# Analog_Input.net
KiCad netlist of a schematic drawn in Altium Designer
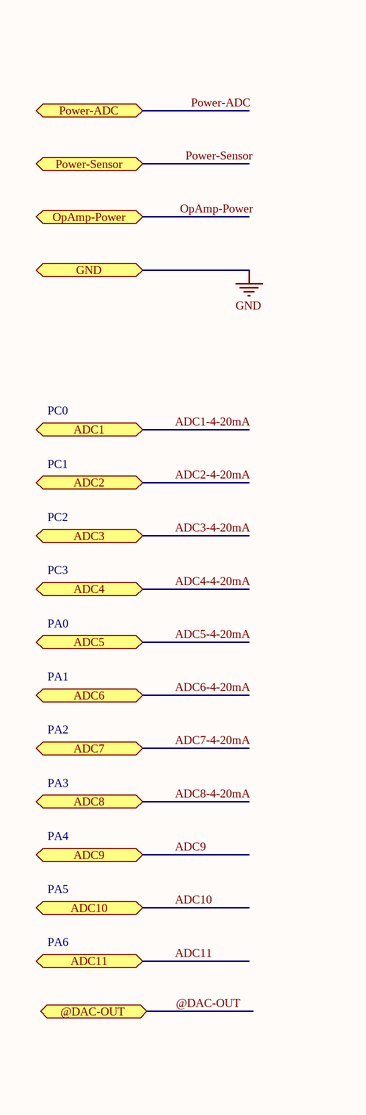
[diagram p0: Analog_Input.SchDoc, top left]
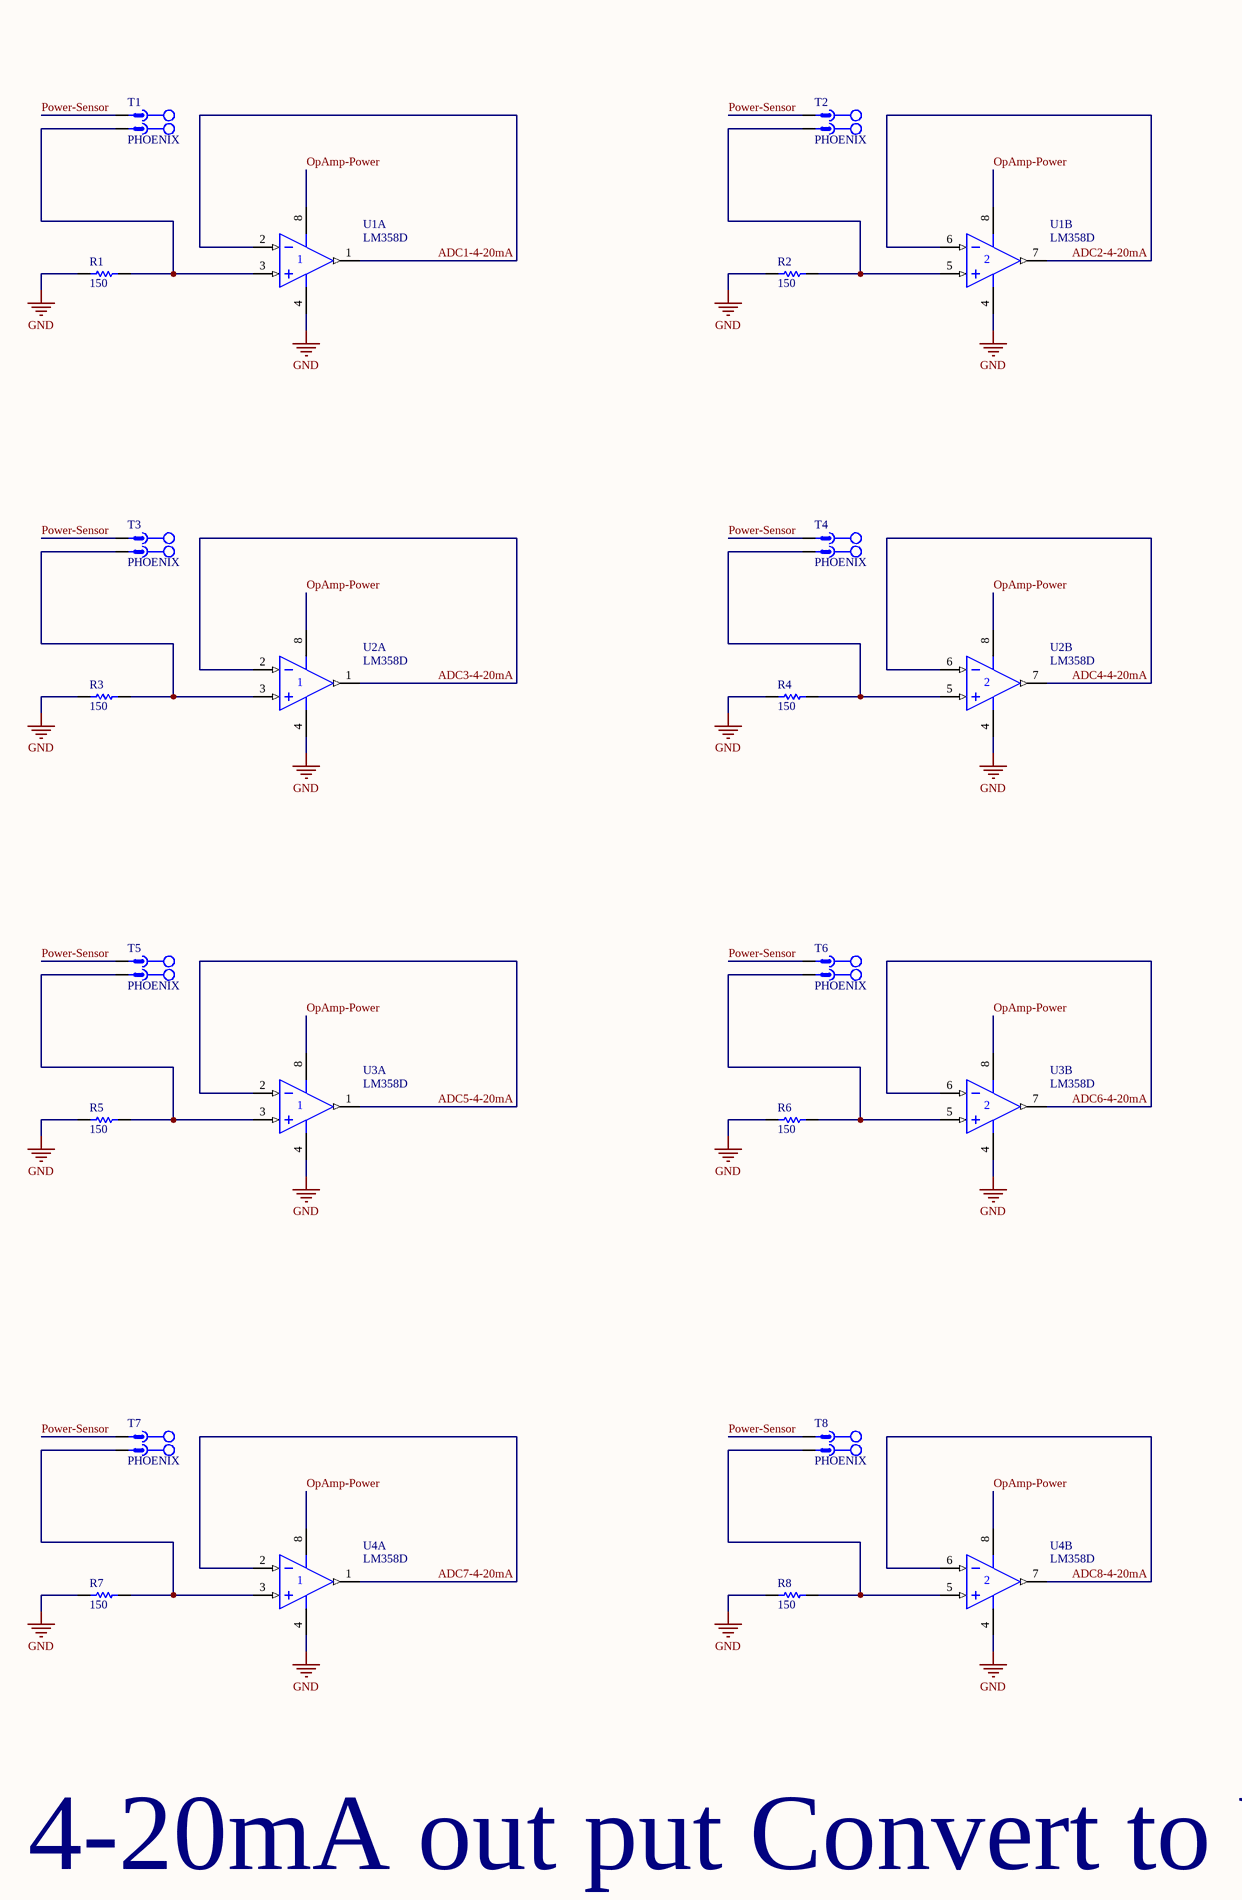
[diagram p1: Analog_Input.SchDoc, top right]
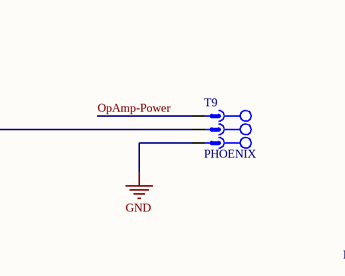
[diagram p2: Analog_Input.SchDoc, bottom left]
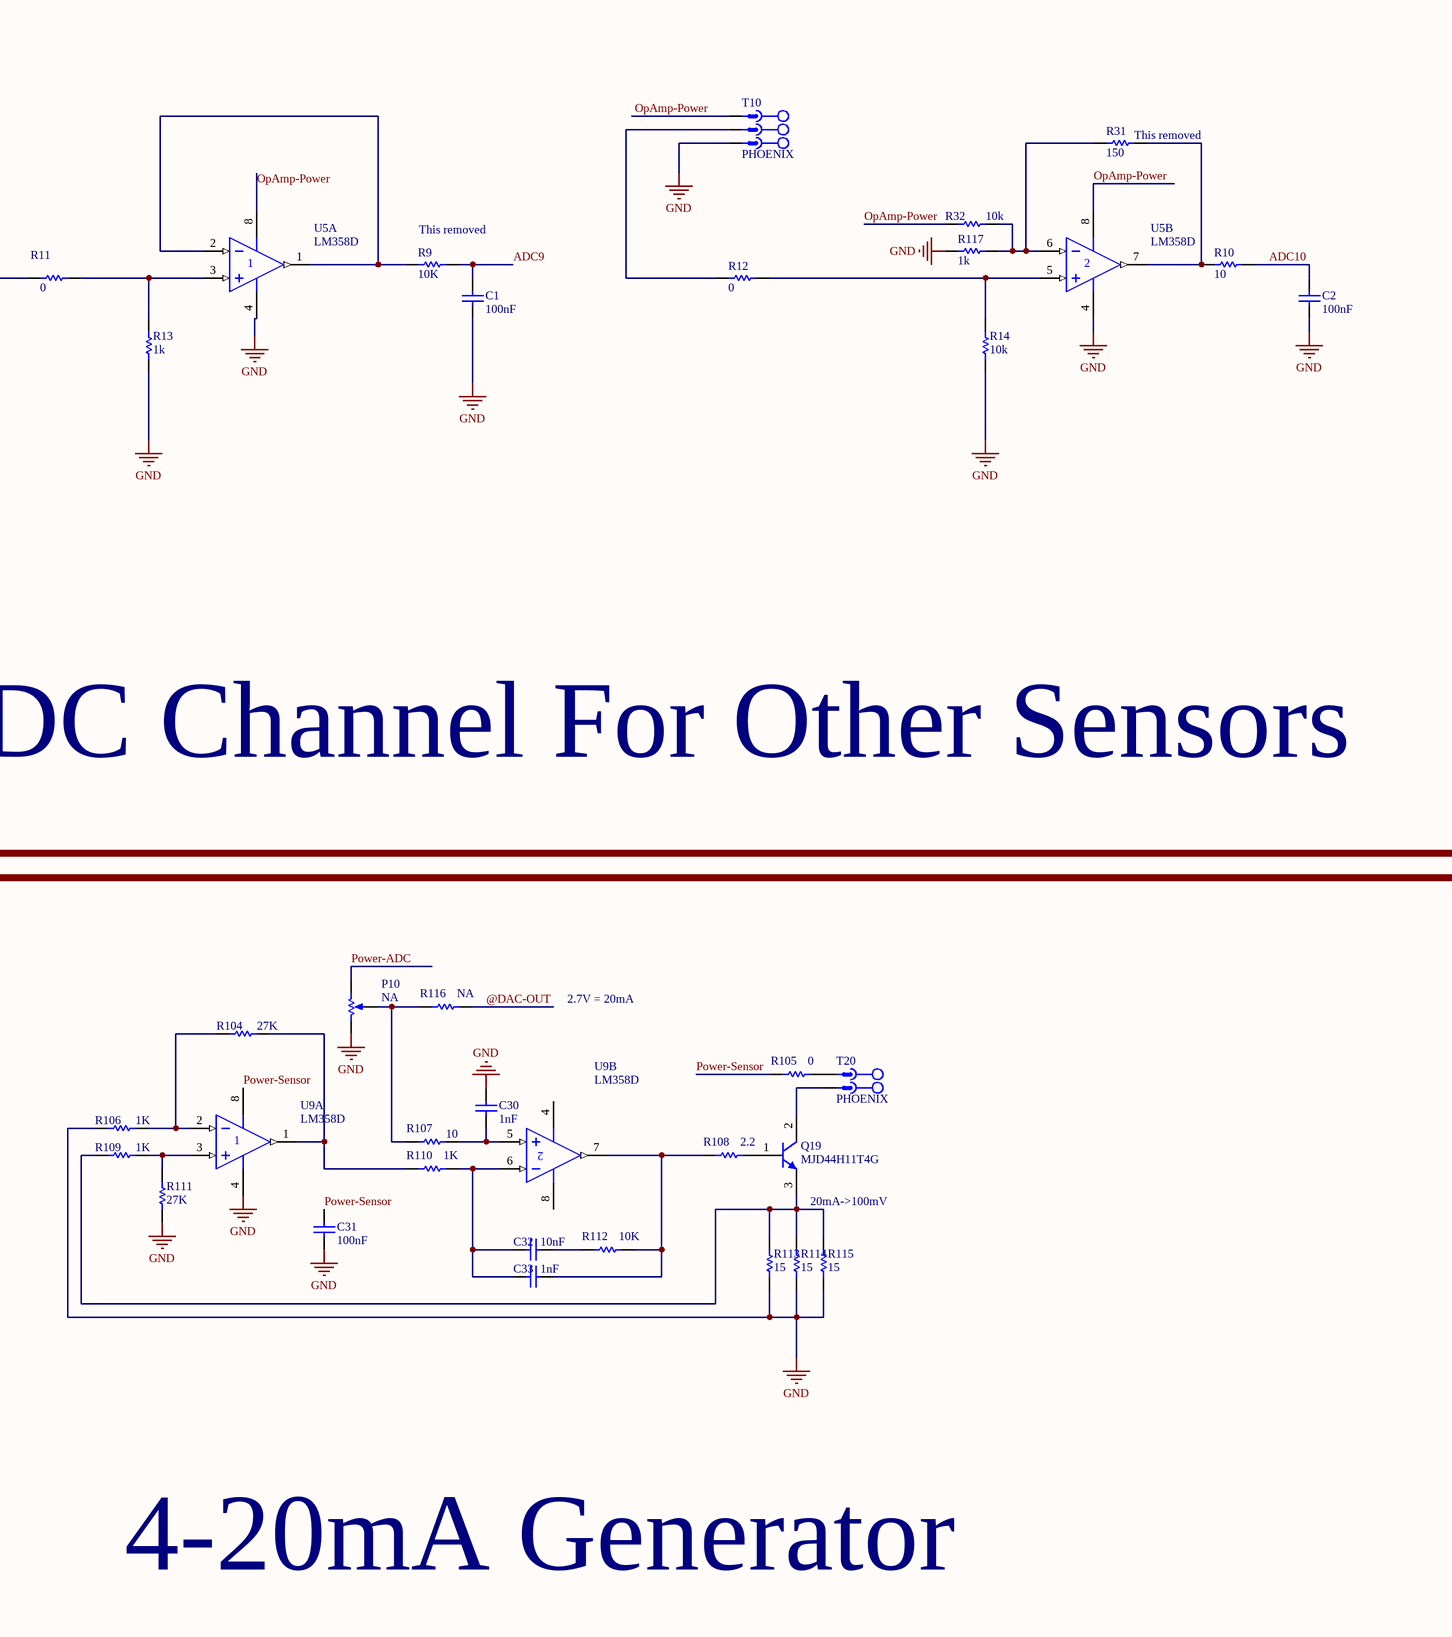
[diagram p3: Analog_Input.SchDoc, bottom right]

(export (version "E")
  (design (tool "Eeschema 10.0.6"))
  (components
    (comp (ref "C1")
      (value "100nF")
      (footprint "CAPC3413X12N")
      (description "CAP 0805")
      (fields (field (name "DESIGNER") "Abbas Basereh"))
      (libsource (lib "Altium") (part "CAP SMD 0805"))
    )
    (comp (ref "C2")
      (value "100nF")
      (footprint "CAPC3413X12N")
      (description "CAP 0805")
      (fields (field (name "DESIGNER") "Abbas Basereh"))
      (libsource (lib "Altium") (part "CAP SMD 0805"))
    )
    (comp (ref "C30")
      (value "1nF")
      (footprint "CAPC3413X12N")
      (description "CAP 0805")
      (fields (field (name "DESIGNER") "Abbas Basereh"))
      (libsource (lib "Altium") (part "CAP SMD 0805"))
    )
    (comp (ref "C31")
      (value "100nF")
      (footprint "CAPC3413X12N")
      (description "CAP 0805")
      (fields (field (name "DESIGNER") "Abbas Basereh"))
      (libsource (lib "Altium") (part "CAP SMD 0805"))
    )
    (comp (ref "C32")
      (value "10nF")
      (footprint "CAPC3413X12N")
      (description "CAP 0805")
      (fields (field (name "DESIGNER") "Abbas Basereh"))
      (libsource (lib "Altium") (part "CAP SMD 0805"))
    )
    (comp (ref "C33")
      (value "1nF")
      (footprint "CAPC3413X12N")
      (description "CAP 0805")
      (fields (field (name "DESIGNER") "Abbas Basereh"))
      (libsource (lib "Altium") (part "CAP SMD 0805"))
    )
    (comp (ref "P10")
      (value "NA")
      (footprint "Multi Turn 02")
      (description "Potentiometer")
      (libsource (lib "My_LIB") (part "Multi-Turn"))
    )
    (comp (ref "Q19") (value "MJD44H11T4G") (footprint "DPACK-SMD") (libsource (lib "Schlib1") (part "NPN")))
    (comp (ref "R1")
      (value "150")
      (footprint "RESC3413X04N")
      (description "RES 0805")
      (fields (field (name "DESIGNER") "Abbas Basereh"))
      (libsource (lib "Altium") (part "RES 0805 0.125W"))
    )
    (comp (ref "R2")
      (value "150")
      (footprint "RESC3413X04N")
      (description "RES 0805")
      (fields (field (name "DESIGNER") "Abbas Basereh"))
      (libsource (lib "Altium") (part "RES 0805 0.125W"))
    )
    (comp (ref "R3")
      (value "150")
      (footprint "RESC3413X04N")
      (description "RES 0805")
      (fields (field (name "DESIGNER") "Abbas Basereh"))
      (libsource (lib "Altium") (part "RES 0805 0.125W"))
    )
    (comp (ref "R4")
      (value "150")
      (footprint "RESC3413X04N")
      (description "RES 0805")
      (fields (field (name "DESIGNER") "Abbas Basereh"))
      (libsource (lib "Altium") (part "RES 0805 0.125W"))
    )
    (comp (ref "R5")
      (value "150")
      (footprint "RESC3413X04N")
      (description "RES 0805")
      (fields (field (name "DESIGNER") "Abbas Basereh"))
      (libsource (lib "Altium") (part "RES 0805 0.125W"))
    )
    (comp (ref "R6")
      (value "150")
      (footprint "RESC3413X04N")
      (description "RES 0805")
      (fields (field (name "DESIGNER") "Abbas Basereh"))
      (libsource (lib "Altium") (part "RES 0805 0.125W"))
    )
    (comp (ref "R7")
      (value "150")
      (footprint "RESC3413X04N")
      (description "RES 0805")
      (fields (field (name "DESIGNER") "Abbas Basereh"))
      (libsource (lib "Altium") (part "RES 0805 0.125W"))
    )
    (comp (ref "R8")
      (value "150")
      (footprint "RESC3413X04N")
      (description "RES 0805")
      (fields (field (name "DESIGNER") "Abbas Basereh"))
      (libsource (lib "Altium") (part "RES 0805 0.125W"))
    )
    (comp (ref "R9")
      (value "10K")
      (footprint "RESC3413X04N")
      (description "RES 0805")
      (fields (field (name "DESIGNER") "Abbas Basereh"))
      (libsource (lib "") (part "RES 0805 0.125W_1"))
    )
    (comp (ref "R10")
      (value "10")
      (footprint "RESC3413X04N")
      (description "RES 0805")
      (fields (field (name "DESIGNER") "Abbas Basereh"))
      (libsource (lib "") (part "RES 0805 0.125W_1"))
    )
    (comp (ref "R11")
      (value "0")
      (footprint "RESC3413X04N")
      (description "RES 0805")
      (fields (field (name "DESIGNER") "Abbas Basereh"))
      (libsource (lib "Altium") (part "RES 0805 0.125W"))
    )
    (comp (ref "R12")
      (value "0")
      (footprint "RESC3413X04N")
      (description "RES 0805")
      (fields (field (name "DESIGNER") "Abbas Basereh"))
      (libsource (lib "Altium") (part "RES 0805 0.125W"))
    )
    (comp (ref "R13")
      (value "1k")
      (footprint "RESC3413X04N")
      (description "RES 0805")
      (fields (field (name "DESIGNER") "Abbas Basereh"))
      (libsource (lib "Altium") (part "RES 0805 0.125W"))
    )
    (comp (ref "R14")
      (value "10k")
      (footprint "RESC3413X04N")
      (description "RES 0805")
      (fields (field (name "DESIGNER") "Abbas Basereh"))
      (libsource (lib "Altium") (part "RES 0805 0.125W"))
    )
    (comp (ref "R31")
      (value "150")
      (footprint "RESC3413X04N")
      (description "RES 0805")
      (fields (field (name "DESIGNER") "Abbas Basereh"))
      (libsource (lib "Altium") (part "RES 0805 0.125W"))
    )
    (comp (ref "R32")
      (value "10k")
      (footprint "RESC3413X04N")
      (description "RES 0805")
      (fields (field (name "DESIGNER") "Abbas Basereh"))
      (libsource (lib "Altium") (part "RES 0805 0.125W"))
    )
    (comp (ref "R104")
      (value "27K")
      (footprint "RESC3413X04N")
      (description "RES 0805")
      (fields (field (name "DESIGNER") "Abbas Basereh"))
      (libsource (lib "Altium") (part "RES 0805 0.125W"))
    )
    (comp (ref "R105")
      (value "0")
      (footprint "RESC3413X04N")
      (description "RES 0805")
      (fields (field (name "DESIGNER") "Abbas Basereh"))
      (libsource (lib "Altium") (part "RES 0805 0.125W"))
    )
    (comp (ref "R106")
      (value "1K")
      (footprint "RESC3413X04N")
      (description "RES 0805")
      (fields (field (name "DESIGNER") "Abbas Basereh"))
      (libsource (lib "Altium") (part "RES 0805 0.125W"))
    )
    (comp (ref "R107")
      (value "10")
      (footprint "RESC3413X04N")
      (description "RES 0805")
      (fields (field (name "DESIGNER") "Abbas Basereh"))
      (libsource (lib "Altium") (part "RES 0805 0.125W"))
    )
    (comp (ref "R108")
      (value "2.2")
      (footprint "RESC3413X04N")
      (description "RES 0805")
      (fields (field (name "DESIGNER") "Abbas Basereh"))
      (libsource (lib "Altium") (part "RES 0805 0.125W"))
    )
    (comp (ref "R109")
      (value "1K")
      (footprint "RESC3413X04N")
      (description "RES 0805")
      (fields (field (name "DESIGNER") "Abbas Basereh"))
      (libsource (lib "Altium") (part "RES 0805 0.125W"))
    )
    (comp (ref "R110")
      (value "1K")
      (footprint "RESC3413X04N")
      (description "RES 0805")
      (fields (field (name "DESIGNER") "Abbas Basereh"))
      (libsource (lib "Altium") (part "RES 0805 0.125W"))
    )
    (comp (ref "R111")
      (value "27K")
      (footprint "RESC3413X04N")
      (description "RES 0805")
      (fields (field (name "DESIGNER") "Abbas Basereh"))
      (libsource (lib "Altium") (part "RES 0805 0.125W"))
    )
    (comp (ref "R112")
      (value "10K")
      (footprint "RESC3413X04N")
      (description "RES 0805")
      (fields (field (name "DESIGNER") "Abbas Basereh"))
      (libsource (lib "Altium") (part "RES 0805 0.125W"))
    )
    (comp (ref "R113")
      (value "15")
      (footprint "RESC3413X04N")
      (description "RES 0805")
      (fields (field (name "DESIGNER") "Abbas Basereh"))
      (libsource (lib "Altium") (part "RES 0805 0.125W"))
    )
    (comp (ref "R114")
      (value "15")
      (footprint "RESC3413X04N")
      (description "RES 0805")
      (fields (field (name "DESIGNER") "Abbas Basereh"))
      (libsource (lib "Altium") (part "RES 0805 0.125W"))
    )
    (comp (ref "R115")
      (value "15")
      (footprint "RESC3413X04N")
      (description "RES 0805")
      (fields (field (name "DESIGNER") "Abbas Basereh"))
      (libsource (lib "Altium") (part "RES 0805 0.125W"))
    )
    (comp (ref "R116")
      (value "NA")
      (footprint "RESC3413X04N")
      (description "RES 0805")
      (fields (field (name "DESIGNER") "Abbas Basereh"))
      (libsource (lib "Altium") (part "RES 0805 0.125W"))
    )
    (comp (ref "R117")
      (value "1k")
      (footprint "RESC3413X04N")
      (description "RES 0805")
      (fields (field (name "DESIGNER") "Abbas Basereh"))
      (libsource (lib "Altium") (part "RES 0805 0.125W"))
    )
    (comp (ref "T1")
      (value "PHOENIX")
      (footprint "MSTB 2,5/2-G-5,08")
      (description "2 Pitch: 5.08 mm Color: green Contact surface: Tin Assembly")
      (fields
        (field (name "MANUFACTURER") "PHOENIX CONTACT")
        (field (name "VOLTAGE") "320 V")
        (field (name "DESIGNER") "ABBAS BASEREH")
      )
      (libsource (lib "Altium") (part "CON_Phoenix_MSTB_02"))
    )
    (comp (ref "T2")
      (value "PHOENIX")
      (footprint "MSTB 2,5/2-G-5,08")
      (description "2 Pitch: 5.08 mm Color: green Contact surface: Tin Assembly")
      (fields
        (field (name "MANUFACTURER") "PHOENIX CONTACT")
        (field (name "VOLTAGE") "320 V")
        (field (name "DESIGNER") "ABBAS BASEREH")
      )
      (libsource (lib "Altium") (part "CON_Phoenix_MSTB_02"))
    )
    (comp (ref "T3")
      (value "PHOENIX")
      (footprint "MSTB 2,5/2-G-5,08")
      (description "2 Pitch: 5.08 mm Color: green Contact surface: Tin Assembly")
      (fields
        (field (name "MANUFACTURER") "PHOENIX CONTACT")
        (field (name "VOLTAGE") "320 V")
        (field (name "DESIGNER") "ABBAS BASEREH")
      )
      (libsource (lib "Altium") (part "CON_Phoenix_MSTB_02"))
    )
    (comp (ref "T4")
      (value "PHOENIX")
      (footprint "MSTB 2,5/2-G-5,08")
      (description "2 Pitch: 5.08 mm Color: green Contact surface: Tin Assembly")
      (fields
        (field (name "MANUFACTURER") "PHOENIX CONTACT")
        (field (name "VOLTAGE") "320 V")
        (field (name "DESIGNER") "ABBAS BASEREH")
      )
      (libsource (lib "Altium") (part "CON_Phoenix_MSTB_02"))
    )
    (comp (ref "T5")
      (value "PHOENIX")
      (footprint "MSTB 2,5/2-G-5,08")
      (description "2 Pitch: 5.08 mm Color: green Contact surface: Tin Assembly")
      (fields
        (field (name "MANUFACTURER") "PHOENIX CONTACT")
        (field (name "VOLTAGE") "320 V")
        (field (name "DESIGNER") "ABBAS BASEREH")
      )
      (libsource (lib "Altium") (part "CON_Phoenix_MSTB_02"))
    )
    (comp (ref "T6")
      (value "PHOENIX")
      (footprint "MSTB 2,5/2-G-5,08")
      (description "2 Pitch: 5.08 mm Color: green Contact surface: Tin Assembly")
      (fields
        (field (name "MANUFACTURER") "PHOENIX CONTACT")
        (field (name "VOLTAGE") "320 V")
        (field (name "DESIGNER") "ABBAS BASEREH")
      )
      (libsource (lib "Altium") (part "CON_Phoenix_MSTB_02"))
    )
    (comp (ref "T7")
      (value "PHOENIX")
      (footprint "MSTB 2,5/2-G-5,08")
      (description "2 Pitch: 5.08 mm Color: green Contact surface: Tin Assembly")
      (fields
        (field (name "MANUFACTURER") "PHOENIX CONTACT")
        (field (name "VOLTAGE") "320 V")
        (field (name "DESIGNER") "ABBAS BASEREH")
      )
      (libsource (lib "Altium") (part "CON_Phoenix_MSTB_02"))
    )
    (comp (ref "T8")
      (value "PHOENIX")
      (footprint "MSTB 2,5/2-G-5,08")
      (description "2 Pitch: 5.08 mm Color: green Contact surface: Tin Assembly")
      (fields
        (field (name "MANUFACTURER") "PHOENIX CONTACT")
        (field (name "VOLTAGE") "320 V")
        (field (name "DESIGNER") "ABBAS BASEREH")
      )
      (libsource (lib "Altium") (part "CON_Phoenix_MSTB_02"))
    )
    (comp (ref "T9")
      (value "PHOENIX")
      (footprint "MSTB 2,5/3-G-5,08")
      (description "3 Pitch: 5.08 mm Color: green Contact surface: Tin Assembly")
      (fields
        (field (name "MANUFACTURER") "PHOENIX CONTACT")
        (field (name "VOLTAGE") "320 V")
        (field (name "DESIGNER") "ABBAS BASEREH")
      )
      (libsource (lib "Altium") (part "CON_Phoenix_MSTB_03"))
    )
    (comp (ref "T10")
      (value "PHOENIX")
      (footprint "MSTB 2,5/3-G-5,08")
      (description "3 Pitch: 5.08 mm Color: green Contact surface: Tin Assembly")
      (fields
        (field (name "MANUFACTURER") "PHOENIX CONTACT")
        (field (name "VOLTAGE") "320 V")
        (field (name "DESIGNER") "ABBAS BASEREH")
      )
      (libsource (lib "Altium") (part "CON_Phoenix_MSTB_03"))
    )
    (comp (ref "T20")
      (value "PHOENIX")
      (footprint "MSTB 2,5/2-G-5,08")
      (description "2 Pitch: 5.08 mm Color: green Contact surface: Tin Assembly")
      (fields
        (field (name "MANUFACTURER") "PHOENIX CONTACT")
        (field (name "VOLTAGE") "320 V")
        (field (name "DESIGNER") "ABBAS BASEREH")
      )
      (libsource (lib "Altium") (part "CON_Phoenix_MSTB_02"))
    )
    (comp (ref "U1")
      (value "LM358D")
      (footprint "SO-8_N")
      (description "Dual Low-Power Operational Amplifier")
      (fields (field (name "PUBLISHER") "Altium Limited"))
      (libsource (lib "My_LIB") (part "LM358D"))
    )
    (comp (ref "U2")
      (value "LM358D")
      (footprint "SO-8_N")
      (description "Dual Low-Power Operational Amplifier")
      (fields (field (name "PUBLISHER") "Altium Limited"))
      (libsource (lib "My_LIB") (part "LM358D"))
    )
    (comp (ref "U3")
      (value "LM358D")
      (footprint "SO-8_N")
      (description "Dual Low-Power Operational Amplifier")
      (fields (field (name "PUBLISHER") "Altium Limited"))
      (libsource (lib "My_LIB") (part "LM358D"))
    )
    (comp (ref "U4")
      (value "LM358D")
      (footprint "SO-8_N")
      (description "Dual Low-Power Operational Amplifier")
      (fields (field (name "PUBLISHER") "Altium Limited"))
      (libsource (lib "My_LIB") (part "LM358D"))
    )
    (comp (ref "U5")
      (value "LM358D")
      (footprint "SO-8_N")
      (description "Dual Low-Power Operational Amplifier")
      (fields (field (name "PUBLISHER") "Altium Limited"))
      (libsource (lib "My_LIB") (part "LM358D"))
    )
    (comp (ref "U9")
      (value "LM358D")
      (footprint "SO-8_N")
      (description "Dual Low-Power Operational Amplifier")
      (fields (field (name "PUBLISHER") "Altium Limited"))
      (libsource (lib "My_LIB") (part "LM358D"))
    )
  )
  (nets
    (net (code "1") (name "/@DAC-OUT") (class "Default")
      (node (ref "R116") (pin "2") (pinfunction "2_2") (pintype "passive"))
    )
    (net (code "2") (name "/ADC1-4-20mA") (class "Default")
      (node (ref "U1") (pin "1") (pinfunction "OUT_1") (pintype "output"))
      (node (ref "U1") (pin "2") (pinfunction "IN-_2") (pintype "input"))
    )
    (net (code "3") (name "/ADC2-4-20mA") (class "Default")
      (node (ref "U1") (pin "6") (pinfunction "IN-_6") (pintype "input"))
      (node (ref "U1") (pin "7") (pinfunction "OUT_7") (pintype "output"))
    )
    (net (code "4") (name "/ADC3-4-20mA") (class "Default")
      (node (ref "U2") (pin "1") (pinfunction "OUT_1") (pintype "output"))
      (node (ref "U2") (pin "2") (pinfunction "IN-_2") (pintype "input"))
    )
    (net (code "5") (name "/ADC4-4-20mA") (class "Default")
      (node (ref "U2") (pin "6") (pinfunction "IN-_6") (pintype "input"))
      (node (ref "U2") (pin "7") (pinfunction "OUT_7") (pintype "output"))
    )
    (net (code "6") (name "/ADC5-4-20mA") (class "Default")
      (node (ref "U3") (pin "1") (pinfunction "OUT_1") (pintype "output"))
      (node (ref "U3") (pin "2") (pinfunction "IN-_2") (pintype "input"))
    )
    (net (code "7") (name "/ADC6-4-20mA") (class "Default")
      (node (ref "U3") (pin "6") (pinfunction "IN-_6") (pintype "input"))
      (node (ref "U3") (pin "7") (pinfunction "OUT_7") (pintype "output"))
    )
    (net (code "8") (name "/ADC7-4-20mA") (class "Default")
      (node (ref "U4") (pin "1") (pinfunction "OUT_1") (pintype "output"))
      (node (ref "U4") (pin "2") (pinfunction "IN-_2") (pintype "input"))
    )
    (net (code "9") (name "/ADC8-4-20mA") (class "Default")
      (node (ref "U4") (pin "6") (pinfunction "IN-_6") (pintype "input"))
      (node (ref "U4") (pin "7") (pinfunction "OUT_7") (pintype "output"))
    )
    (net (code "10") (name "/ADC9") (class "Default")
      (node (ref "C1") (pin "2") (pinfunction "2_2") (pintype "passive"))
      (node (ref "R9") (pin "1") (pinfunction "1_1") (pintype "passive"))
    )
    (net (code "11") (name "/ADC10") (class "Default")
      (node (ref "C2") (pin "2") (pinfunction "2_2") (pintype "passive"))
      (node (ref "R10") (pin "1") (pinfunction "1_1") (pintype "passive"))
    )
    (net (code "13") (name "/OpAmp-Power") (class "Default")
      (node (ref "R32") (pin "2") (pinfunction "2_2") (pintype "passive"))
      (node (ref "T10") (pin "1") (pinfunction "1_1") (pintype "passive"))
      (node (ref "T9") (pin "1") (pinfunction "1_1") (pintype "passive"))
      (node (ref "U1") (pin "8") (pinfunction "V+_8") (pintype "power_in"))
      (node (ref "U2") (pin "8") (pinfunction "V+_8") (pintype "power_in"))
      (node (ref "U3") (pin "8") (pinfunction "V+_8") (pintype "power_in"))
      (node (ref "U4") (pin "8") (pinfunction "V+_8") (pintype "power_in"))
      (node (ref "U5") (pin "8") (pinfunction "V+_8") (pintype "power_in"))
    )
    (net (code "14") (name "/Power-ADC") (class "Default")
      (node (ref "P10") (pin "1") (pinfunction "TOP_1") (pintype "passive"))
    )
    (net (code "15") (name "/Power-Sensor") (class "Default")
      (node (ref "C31") (pin "2") (pinfunction "2_2") (pintype "passive"))
      (node (ref "R105") (pin "1") (pinfunction "1_1") (pintype "passive"))
      (node (ref "T1") (pin "1") (pinfunction "1_1") (pintype "passive"))
      (node (ref "T2") (pin "1") (pinfunction "1_1") (pintype "passive"))
      (node (ref "T3") (pin "1") (pinfunction "1_1") (pintype "passive"))
      (node (ref "T4") (pin "1") (pinfunction "1_1") (pintype "passive"))
      (node (ref "T5") (pin "1") (pinfunction "1_1") (pintype "passive"))
      (node (ref "T6") (pin "1") (pinfunction "1_1") (pintype "passive"))
      (node (ref "T7") (pin "1") (pinfunction "1_1") (pintype "passive"))
      (node (ref "T8") (pin "1") (pinfunction "1_1") (pintype "passive"))
      (node (ref "U9") (pin "8") (pinfunction "V+_8") (pintype "power_in"))
    )
    (net (code "16") (name "GND") (class "Default")
      (node (ref "C1") (pin "1") (pinfunction "1_1") (pintype "passive"))
      (node (ref "C2") (pin "1") (pinfunction "1_1") (pintype "passive"))
      (node (ref "C30") (pin "1") (pinfunction "1_1") (pintype "passive"))
      (node (ref "C31") (pin "1") (pinfunction "1_1") (pintype "passive"))
      (node (ref "P10") (pin "3") (pinfunction "BOT_3") (pintype "passive"))
      (node (ref "R1") (pin "1") (pinfunction "1_1") (pintype "passive"))
      (node (ref "R106") (pin "1") (pinfunction "1_1") (pintype "passive"))
      (node (ref "R111") (pin "1") (pinfunction "1_1") (pintype "passive"))
      (node (ref "R113") (pin "1") (pinfunction "1_1") (pintype "passive"))
      (node (ref "R114") (pin "1") (pinfunction "1_1") (pintype "passive"))
      (node (ref "R115") (pin "1") (pinfunction "1_1") (pintype "passive"))
      (node (ref "R117") (pin "2") (pinfunction "2_2") (pintype "passive"))
      (node (ref "R13") (pin "1") (pinfunction "1_1") (pintype "passive"))
      (node (ref "R14") (pin "1") (pinfunction "1_1") (pintype "passive"))
      (node (ref "R2") (pin "1") (pinfunction "1_1") (pintype "passive"))
      (node (ref "R3") (pin "1") (pinfunction "1_1") (pintype "passive"))
      (node (ref "R4") (pin "1") (pinfunction "1_1") (pintype "passive"))
      (node (ref "R5") (pin "1") (pinfunction "1_1") (pintype "passive"))
      (node (ref "R6") (pin "1") (pinfunction "1_1") (pintype "passive"))
      (node (ref "R7") (pin "1") (pinfunction "1_1") (pintype "passive"))
      (node (ref "R8") (pin "1") (pinfunction "1_1") (pintype "passive"))
      (node (ref "T10") (pin "3") (pinfunction "3_3") (pintype "passive"))
      (node (ref "T9") (pin "3") (pinfunction "3_3") (pintype "passive"))
      (node (ref "U1") (pin "4") (pinfunction "V-_4") (pintype "power_in"))
      (node (ref "U2") (pin "4") (pinfunction "V-_4") (pintype "power_in"))
      (node (ref "U3") (pin "4") (pinfunction "V-_4") (pintype "power_in"))
      (node (ref "U4") (pin "4") (pinfunction "V-_4") (pintype "power_in"))
      (node (ref "U5") (pin "4") (pinfunction "V-_4") (pintype "power_in"))
      (node (ref "U9") (pin "4") (pinfunction "V-_4") (pintype "power_in"))
    )
    (net (code "17") (name "Net-(C32-Pad1)") (class "Default")
      (node (ref "C32") (pin "1") (pinfunction "1_1") (pintype "passive"))
      (node (ref "R112") (pin "1") (pinfunction "1_1") (pintype "passive"))
    )
    (net (code "18") (name "Net-(P10-TAP)") (class "Default")
      (node (ref "P10") (pin "2") (pinfunction "TAP_2") (pintype "passive"))
      (node (ref "R107") (pin "1") (pinfunction "1_1") (pintype "passive"))
      (node (ref "R116") (pin "1") (pinfunction "1_1") (pintype "passive"))
    )
    (net (code "19") (name "Net-(Q19-Pad1)") (class "Default")
      (node (ref "Q19") (pin "1") (pinfunction "1_1") (pintype "passive"))
      (node (ref "R108") (pin "2") (pinfunction "2_2") (pintype "passive"))
    )
    (net (code "20") (name "Net-(Q19-Pad2)") (class "Default")
      (node (ref "Q19") (pin "2") (pinfunction "2_2") (pintype "passive"))
      (node (ref "T20") (pin "2") (pinfunction "2_2") (pintype "passive"))
    )
    (net (code "21") (name "Net-(Q19-Pad3)") (class "Default")
      (node (ref "Q19") (pin "3") (pinfunction "3_3") (pintype "passive"))
      (node (ref "R109") (pin "1") (pinfunction "1_1") (pintype "passive"))
      (node (ref "R113") (pin "2") (pinfunction "2_2") (pintype "passive"))
      (node (ref "R114") (pin "2") (pinfunction "2_2") (pintype "passive"))
      (node (ref "R115") (pin "2") (pinfunction "2_2") (pintype "passive"))
    )
    (net (code "22") (name "Net-(R11-Pad1)") (class "Default")
      (node (ref "R11") (pin "1") (pinfunction "1_1") (pintype "passive"))
      (node (ref "T9") (pin "2") (pinfunction "2_2") (pintype "passive"))
    )
    (net (code "23") (name "Net-(R12-Pad1)") (class "Default")
      (node (ref "R12") (pin "1") (pinfunction "1_1") (pintype "passive"))
      (node (ref "T10") (pin "2") (pinfunction "2_2") (pintype "passive"))
    )
    (net (code "24") (name "Net-(R105-Pad2)") (class "Default")
      (node (ref "R105") (pin "2") (pinfunction "2_2") (pintype "passive"))
      (node (ref "T20") (pin "1") (pinfunction "1_1") (pintype "passive"))
    )
    (net (code "25") (name "Net-(U1A-IN+)") (class "Default")
      (node (ref "R1") (pin "2") (pinfunction "2_2") (pintype "passive"))
      (node (ref "T1") (pin "2") (pinfunction "2_2") (pintype "passive"))
      (node (ref "U1") (pin "3") (pinfunction "IN+_3") (pintype "input"))
    )
    (net (code "26") (name "Net-(U1B-IN+)") (class "Default")
      (node (ref "R2") (pin "2") (pinfunction "2_2") (pintype "passive"))
      (node (ref "T2") (pin "2") (pinfunction "2_2") (pintype "passive"))
      (node (ref "U1") (pin "5") (pinfunction "IN+_5") (pintype "input"))
    )
    (net (code "27") (name "Net-(U2A-IN+)") (class "Default")
      (node (ref "R3") (pin "2") (pinfunction "2_2") (pintype "passive"))
      (node (ref "T3") (pin "2") (pinfunction "2_2") (pintype "passive"))
      (node (ref "U2") (pin "3") (pinfunction "IN+_3") (pintype "input"))
    )
    (net (code "28") (name "Net-(U2B-IN+)") (class "Default")
      (node (ref "R4") (pin "2") (pinfunction "2_2") (pintype "passive"))
      (node (ref "T4") (pin "2") (pinfunction "2_2") (pintype "passive"))
      (node (ref "U2") (pin "5") (pinfunction "IN+_5") (pintype "input"))
    )
    (net (code "29") (name "Net-(U3A-IN+)") (class "Default")
      (node (ref "R5") (pin "2") (pinfunction "2_2") (pintype "passive"))
      (node (ref "T5") (pin "2") (pinfunction "2_2") (pintype "passive"))
      (node (ref "U3") (pin "3") (pinfunction "IN+_3") (pintype "input"))
    )
    (net (code "30") (name "Net-(U3B-IN+)") (class "Default")
      (node (ref "R6") (pin "2") (pinfunction "2_2") (pintype "passive"))
      (node (ref "T6") (pin "2") (pinfunction "2_2") (pintype "passive"))
      (node (ref "U3") (pin "5") (pinfunction "IN+_5") (pintype "input"))
    )
    (net (code "31") (name "Net-(U4A-IN+)") (class "Default")
      (node (ref "R7") (pin "2") (pinfunction "2_2") (pintype "passive"))
      (node (ref "T7") (pin "2") (pinfunction "2_2") (pintype "passive"))
      (node (ref "U4") (pin "3") (pinfunction "IN+_3") (pintype "input"))
    )
    (net (code "32") (name "Net-(U4B-IN+)") (class "Default")
      (node (ref "R8") (pin "2") (pinfunction "2_2") (pintype "passive"))
      (node (ref "T8") (pin "2") (pinfunction "2_2") (pintype "passive"))
      (node (ref "U4") (pin "5") (pinfunction "IN+_5") (pintype "input"))
    )
    (net (code "33") (name "Net-(U5A-IN+)") (class "Default")
      (node (ref "R11") (pin "2") (pinfunction "2_2") (pintype "passive"))
      (node (ref "R13") (pin "2") (pinfunction "2_2") (pintype "passive"))
      (node (ref "U5") (pin "3") (pinfunction "IN+_3") (pintype "input"))
    )
    (net (code "34") (name "Net-(U5A-IN-)") (class "Default")
      (node (ref "R9") (pin "2") (pinfunction "2_2") (pintype "passive"))
      (node (ref "U5") (pin "1") (pinfunction "OUT_1") (pintype "output"))
      (node (ref "U5") (pin "2") (pinfunction "IN-_2") (pintype "input"))
    )
    (net (code "35") (name "Net-(U5B-IN+)") (class "Default")
      (node (ref "R12") (pin "2") (pinfunction "2_2") (pintype "passive"))
      (node (ref "R14") (pin "2") (pinfunction "2_2") (pintype "passive"))
      (node (ref "U5") (pin "5") (pinfunction "IN+_5") (pintype "input"))
    )
    (net (code "36") (name "Net-(U5B-IN-)") (class "Default")
      (node (ref "R117") (pin "1") (pinfunction "1_1") (pintype "passive"))
      (node (ref "R31") (pin "2") (pinfunction "2_2") (pintype "passive"))
      (node (ref "R32") (pin "1") (pinfunction "1_1") (pintype "passive"))
      (node (ref "U5") (pin "6") (pinfunction "IN-_6") (pintype "input"))
    )
    (net (code "37") (name "Net-(U5B-OUT)") (class "Default")
      (node (ref "R10") (pin "2") (pinfunction "2_2") (pintype "passive"))
      (node (ref "R31") (pin "1") (pinfunction "1_1") (pintype "passive"))
      (node (ref "U5") (pin "7") (pinfunction "OUT_7") (pintype "output"))
    )
    (net (code "38") (name "Net-(U9A-IN+)") (class "Default")
      (node (ref "R109") (pin "2") (pinfunction "2_2") (pintype "passive"))
      (node (ref "R111") (pin "2") (pinfunction "2_2") (pintype "passive"))
      (node (ref "U9") (pin "3") (pinfunction "IN+_3") (pintype "input"))
    )
    (net (code "39") (name "Net-(U9A-IN-)") (class "Default")
      (node (ref "R104") (pin "1") (pinfunction "1_1") (pintype "passive"))
      (node (ref "R106") (pin "2") (pinfunction "2_2") (pintype "passive"))
      (node (ref "U9") (pin "2") (pinfunction "IN-_2") (pintype "input"))
    )
    (net (code "40") (name "Net-(U9A-OUT)") (class "Default")
      (node (ref "R104") (pin "2") (pinfunction "2_2") (pintype "passive"))
      (node (ref "R110") (pin "1") (pinfunction "1_1") (pintype "passive"))
      (node (ref "U9") (pin "1") (pinfunction "OUT_1") (pintype "output"))
    )
    (net (code "41") (name "Net-(U9B-IN+)") (class "Default")
      (node (ref "C30") (pin "2") (pinfunction "2_2") (pintype "passive"))
      (node (ref "R107") (pin "2") (pinfunction "2_2") (pintype "passive"))
      (node (ref "U9") (pin "5") (pinfunction "IN+_5") (pintype "input"))
    )
    (net (code "42") (name "Net-(U9B-IN-)") (class "Default")
      (node (ref "C32") (pin "2") (pinfunction "2_2") (pintype "passive"))
      (node (ref "C33") (pin "2") (pinfunction "2_2") (pintype "passive"))
      (node (ref "R110") (pin "2") (pinfunction "2_2") (pintype "passive"))
      (node (ref "U9") (pin "6") (pinfunction "IN-_6") (pintype "input"))
    )
    (net (code "43") (name "Net-(U9B-OUT)") (class "Default")
      (node (ref "C33") (pin "1") (pinfunction "1_1") (pintype "passive"))
      (node (ref "R108") (pin "1") (pinfunction "1_1") (pintype "passive"))
      (node (ref "R112") (pin "2") (pinfunction "2_2") (pintype "passive"))
      (node (ref "U9") (pin "7") (pinfunction "OUT_7") (pintype "output"))
    )
    (net (code "44") (name "unconnected-(U9B-V+-Pad8)") (class "Default")
      (node (ref "U9") (pin "8") (pinfunction "V+_8") (pintype "power_in"))
    )
    (net (code "45") (name "unconnected-(U9B-V--Pad4)") (class "Default")
      (node (ref "U9") (pin "4") (pinfunction "V-_4") (pintype "power_in"))
    )
  )
)
